# BLUETOOTH_UNIT.net
KiCad netlist of a schematic drawn in EAGLE
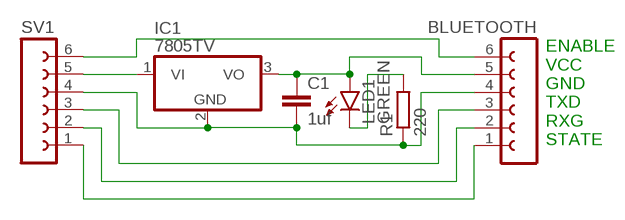
[diagram p0: schematic, sheet 1]

(export (version "E")
  (design (tool "Eeschema 10.0.6"))
  (components
    (comp (ref "BLUETOOTH")
      (value "FE06-1")
      (footprint "eagle-import:FE06")
      (libsource (lib "eagle-import") (part "FE06-1"))
    )
    (comp (ref "C1")
      (value "1uf")
      (footprint "eagle-import:C025-025X050")
      (libsource (lib "eagle-import") (part "C-EU025-025X050"))
    )
    (comp (ref "IC1")
      (value "7805TV")
      (footprint "eagle-import:TO220V")
      (libsource (lib "eagle-import") (part "78TV05"))
    )
    (comp (ref "LED1")
      (value "GREEN")
      (footprint "eagle-import:SML0805")
      (libsource (lib "eagle-import") (part "LEDSML0805"))
    )
    (comp (ref "R1")
      (value "220")
      (footprint "eagle-import:0204_7")
      (libsource (lib "eagle-import") (part "R-EU_0204/7"))
    )
    (comp (ref "SV1")
      (value "FE06-1")
      (footprint "eagle-import:FE06")
      (libsource (lib "eagle-import") (part "FE06-1"))
    )
  )
  (nets
    (net (code "1") (name "Net-(BLUETOOTH-Pad1)") (class "Default")
      (node (ref "BLUETOOTH") (pin "1") (pinfunction "1_1") (pintype "passive"))
      (node (ref "SV1") (pin "1") (pinfunction "1_1") (pintype "passive"))
    )
    (net (code "2") (name "Net-(BLUETOOTH-Pad2)") (class "Default")
      (node (ref "BLUETOOTH") (pin "2") (pinfunction "2_2") (pintype "passive"))
      (node (ref "SV1") (pin "2") (pinfunction "2_2") (pintype "passive"))
    )
    (net (code "3") (name "Net-(BLUETOOTH-Pad3)") (class "Default")
      (node (ref "BLUETOOTH") (pin "3") (pinfunction "3_3") (pintype "passive"))
      (node (ref "SV1") (pin "3") (pinfunction "3_3") (pintype "passive"))
    )
    (net (code "4") (name "Net-(BLUETOOTH-Pad6)") (class "Default")
      (node (ref "BLUETOOTH") (pin "6") (pinfunction "6_6") (pintype "passive"))
      (node (ref "SV1") (pin "6") (pinfunction "6_6") (pintype "passive"))
    )
    (net (code "5") (name "Net-(IC1-GND)") (class "Default")
      (node (ref "BLUETOOTH") (pin "4") (pinfunction "4_4") (pintype "passive"))
      (node (ref "C1") (pin "2") (pinfunction "2_2") (pintype "passive"))
      (node (ref "IC1") (pin "2") (pinfunction "GND_2") (pintype "passive"))
      (node (ref "R1") (pin "1") (pinfunction "1_1") (pintype "passive"))
      (node (ref "SV1") (pin "4") (pinfunction "4_4") (pintype "passive"))
    )
    (net (code "6") (name "Net-(IC1-VI)") (class "Default")
      (node (ref "IC1") (pin "1") (pinfunction "VI_1") (pintype "input"))
      (node (ref "SV1") (pin "5") (pinfunction "5_5") (pintype "passive"))
    )
    (net (code "7") (name "Net-(IC1-VO)") (class "Default")
      (node (ref "BLUETOOTH") (pin "5") (pinfunction "5_5") (pintype "passive"))
      (node (ref "C1") (pin "1") (pinfunction "1_1") (pintype "passive"))
      (node (ref "IC1") (pin "3") (pinfunction "VO_3") (pintype "passive"))
      (node (ref "LED1") (pin "A") (pinfunction "A_A") (pintype "passive"))
    )
    (net (code "8") (name "Net-(LED1-PadC)") (class "Default")
      (node (ref "LED1") (pin "C") (pinfunction "C_C") (pintype "passive"))
      (node (ref "R1") (pin "2") (pinfunction "2_2") (pintype "passive"))
    )
  )
)
